# E-41_LIDAR_Dev_Brd.net
KiCad netlist of a schematic drawn in Altium Designer
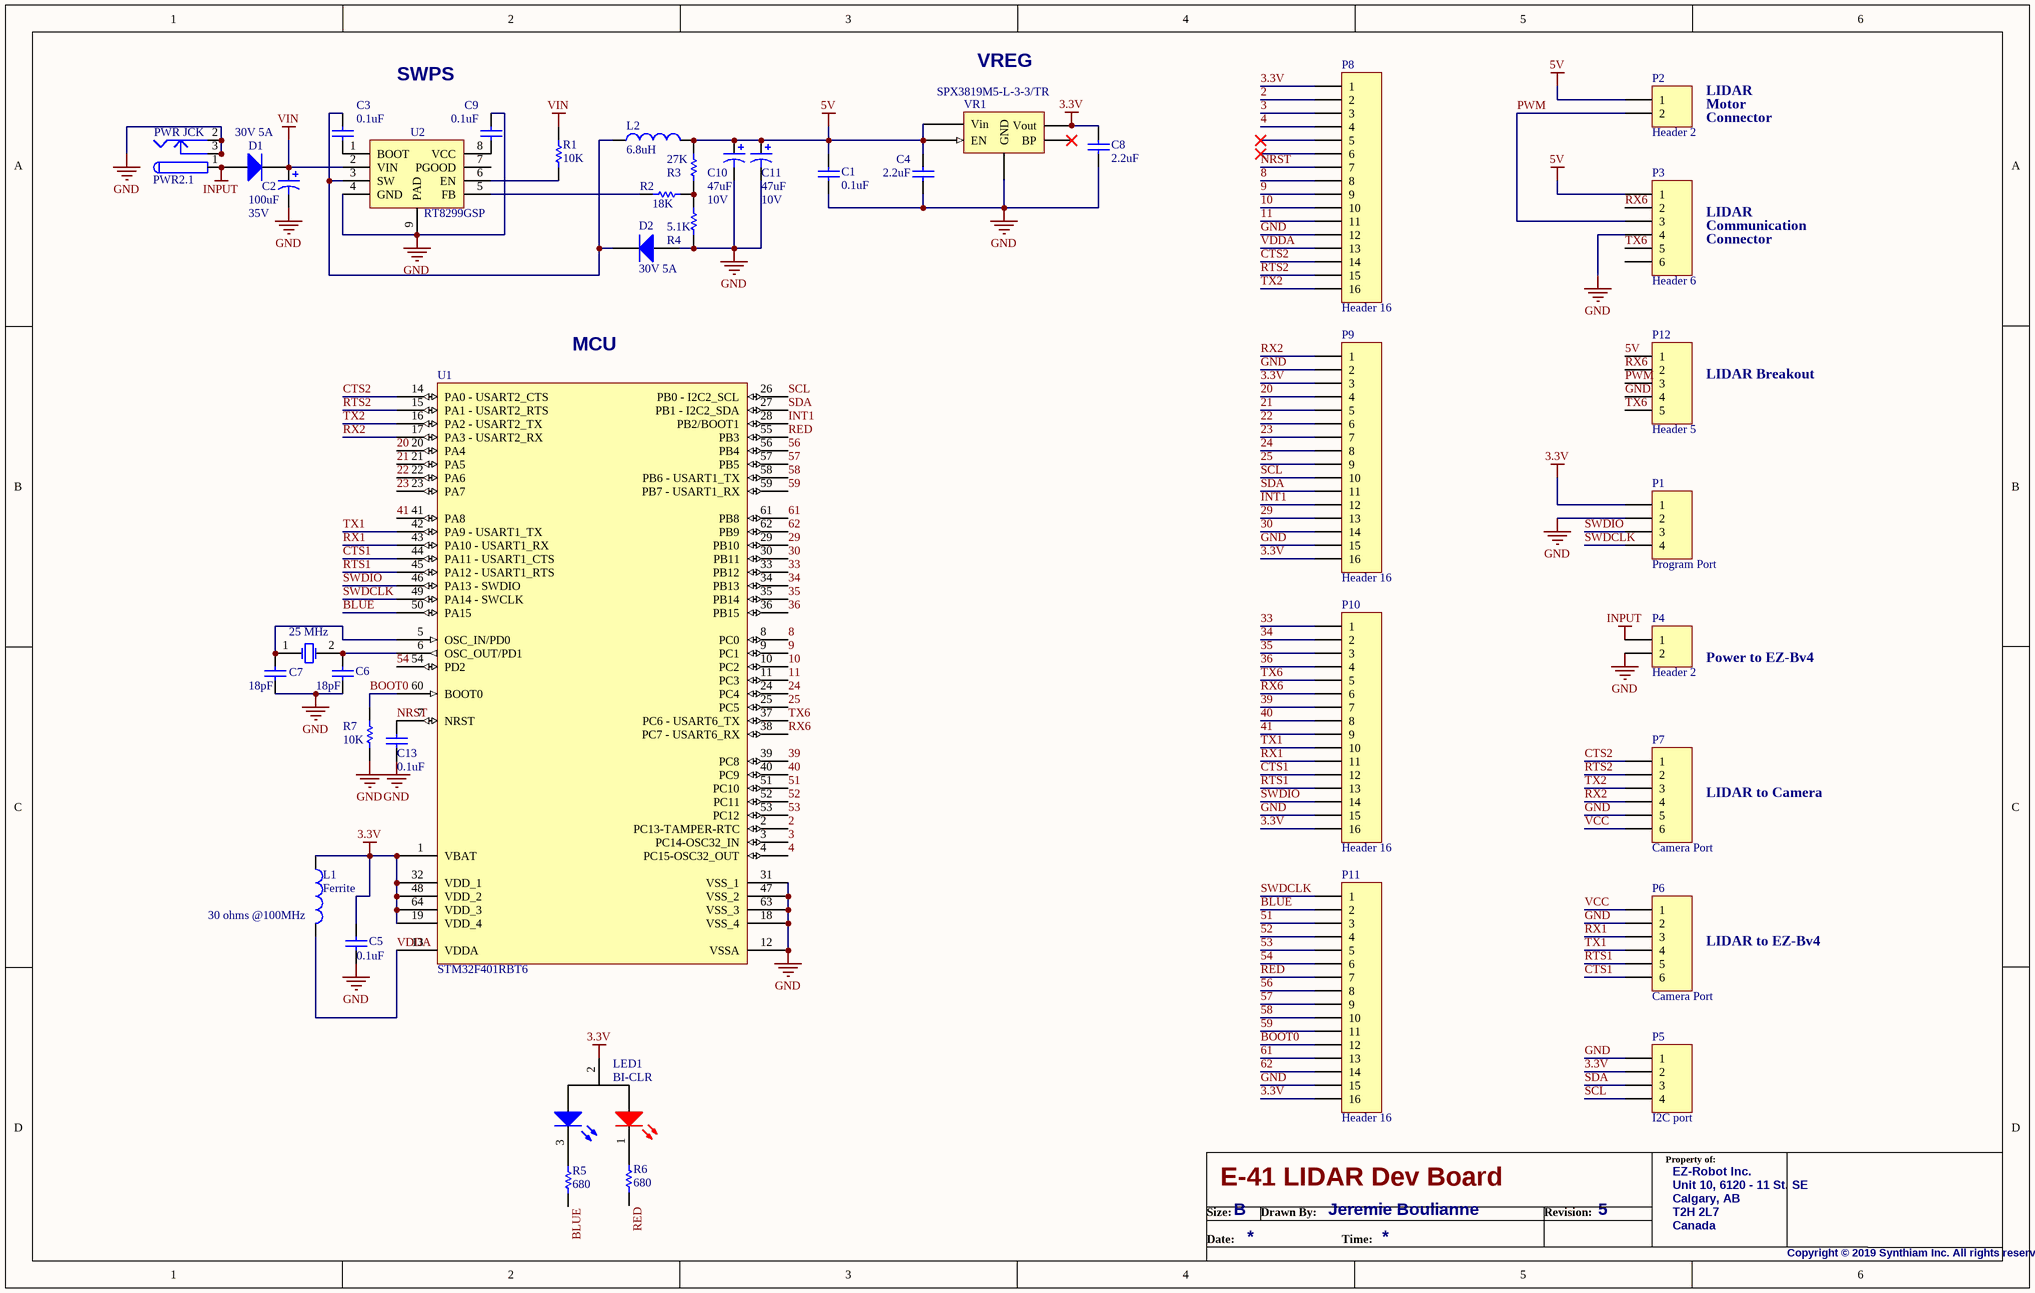
[diagram p0: E-41 LIDAR Dev Brd.SchDoc]

(export (version "E")
  (design (tool "Eeschema 10.0.6"))
  (components
    (comp (ref "25 MHz")
      (value "XTAL")
      (footprint "Crystal")
      (description "Crystal Oscillator")
      (fields (field (name "PUBLISHER") "Altium Limited"))
      (libsource (lib "SB_Discrete") (part "XTAL"))
    )
    (comp (ref "C1")
      (value "0.1uF")
      (footprint "0603 TIGHT")
      (description "Capacitor")
      (fields (field (name "Comment") "Cap") (field (name "PUBLISHER") "Altium Limited"))
      (libsource (lib "SB_Discrete") (part "Cap"))
    )
    (comp (ref "C2")
      (value "35V")
      (footprint "SMD Capacitor 220uf 16V")
      (description "Polarized Capacitor (Radial)")
      (fields (field (name "ALTIUM_VALUE") "100uF") (field (name "PUBLISHER") "Altium Limited"))
      (libsource (lib "Miscellaneous Devices") (part "Cap Pol1"))
    )
    (comp (ref "C3")
      (value "0.1uF")
      (footprint "0603 TIGHT")
      (description "Capacitor")
      (fields (field (name "PUBLISHER") "Altium Limited"))
      (libsource (lib "SB_Discrete") (part "Cap"))
    )
    (comp (ref "C4")
      (value "2.2uF")
      (footprint "0603 TIGHT")
      (description "Capacitor")
      (fields (field (name "Comment") "Cap") (field (name "PUBLISHER") "Altium Limited"))
      (libsource (lib "SB_Discrete") (part "Cap"))
    )
    (comp (ref "C5")
      (value "0.1uF")
      (footprint "0603 TIGHT")
      (description "Capacitor")
      (fields (field (name "Comment") "Cap") (field (name "PUBLISHER") "Altium Limited"))
      (libsource (lib "SB_Discrete") (part "Cap"))
    )
    (comp (ref "C6")
      (value "18pF")
      (footprint "0603 TIGHT")
      (description "Capacitor")
      (fields (field (name "Comment") "Cap") (field (name "PUBLISHER") "Altium Limited"))
      (libsource (lib "SB_Discrete") (part "Cap"))
    )
    (comp (ref "C7")
      (value "18pF")
      (footprint "0603 TIGHT")
      (description "Capacitor")
      (fields (field (name "Comment") "Cap") (field (name "PUBLISHER") "Altium Limited"))
      (libsource (lib "SB_Discrete") (part "Cap"))
    )
    (comp (ref "C8")
      (value "2.2uF")
      (footprint "0603 TIGHT")
      (description "Capacitor")
      (fields (field (name "Comment") "Cap") (field (name "PUBLISHER") "Altium Limited"))
      (libsource (lib "SB_Discrete") (part "Cap"))
    )
    (comp (ref "C9")
      (value "0.1uF")
      (footprint "0603 TIGHT")
      (description "Capacitor")
      (fields (field (name "Comment") "Cap") (field (name "PUBLISHER") "Altium Limited"))
      (libsource (lib "SB_Discrete") (part "Cap"))
    )
    (comp (ref "C10")
      (value "10V")
      (footprint "1206")
      (description "Polarized Capacitor (Radial)")
      (fields (field (name "ALTIUM_VALUE") "47uF") (field (name "PUBLISHER") "Altium Limited"))
      (libsource (lib "Miscellaneous Devices") (part "Cap Pol1"))
    )
    (comp (ref "C11")
      (value "10V")
      (footprint "1206")
      (description "Polarized Capacitor (Radial)")
      (fields (field (name "ALTIUM_VALUE") "47uF") (field (name "PUBLISHER") "Altium Limited"))
      (libsource (lib "Miscellaneous Devices") (part "Cap Pol1"))
    )
    (comp (ref "C13")
      (value "0.1uF")
      (footprint "0603 TIGHT")
      (description "Capacitor")
      (fields (field (name "Comment") "Cap") (field (name "PUBLISHER") "Altium Limited"))
      (libsource (lib "SB_Discrete") (part "Cap"))
    )
    (comp (ref "D1")
      (value "30V 5A")
      (footprint "DIODE SOD-128")
      (description "High Conductance Fast Diode")
      (fields (field (name "PUBLISHER") "Altium Limited"))
      (libsource (lib "Miscellaneous Devices") (part "Diode 1N4148"))
    )
    (comp (ref "D2")
      (value "30V 5A")
      (footprint "DIODE SOD-128")
      (description "High Conductance Fast Diode")
      (fields (field (name "PUBLISHER") "Altium Limited"))
      (libsource (lib "Miscellaneous Devices") (part "Diode 1N4148"))
    )
    (comp (ref "L1")
      (value "Ferrite")
      (footprint "0603 TIGHT")
      (description "Inductor")
      (fields (field (name "ALTIUM_VALUE") "30 ohms @100MHz") (field (name "PUBLISHER") "Altium Limited"))
      (libsource (lib "Miscellaneous Devices") (part "Inductor"))
    )
    (comp (ref "L2")
      (value "6.8uH")
      (footprint "Inductor SMD")
      (description "Inductor")
      (fields (field (name "Comment") "Ferrite") (field (name "PUBLISHER") "Altium Limited"))
      (libsource (lib "Miscellaneous Devices") (part "Inductor"))
    )
    (comp (ref "LED1")
      (value "BI-CLR")
      (footprint "LED BI-COLOR")
      (libsource (lib "SB_Discrete") (part "LED BI-COLOR"))
    )
    (comp (ref "P1")
      (value "Program Port")
      (footprint "HDR1X4")
      (description "Header, 4-Pin")
      (fields (field (name "PUBLISHER") "Altium Limited"))
      (libsource (lib "Miscellaneous Connectors") (part "Header 4"))
    )
    (comp (ref "P2")
      (value "Header 2")
      (footprint "JST-PH 2-pin")
      (description "Header, 2-Pin")
      (fields (field (name "PUBLISHER") "Altium Limited"))
      (libsource (lib "Miscellaneous Connectors") (part "Header 2"))
    )
    (comp (ref "P3")
      (value "Header 6")
      (footprint "JST-GH 6-pin")
      (description "Header, 6-Pin")
      (fields (field (name "PUBLISHER") "Altium Limited"))
      (libsource (lib "Miscellaneous Connectors") (part "Header 6"))
    )
    (comp (ref "P4")
      (value "Header 2")
      (footprint "HDR1X2")
      (description "Header, 2-Pin")
      (fields (field (name "PUBLISHER") "Altium Limited"))
      (libsource (lib "Miscellaneous Connectors") (part "Header 2"))
    )
    (comp (ref "P5")
      (value "I2C port")
      (footprint "JST-PH 4pin")
      (description "Header, 4-Pin")
      (fields (field (name "PUBLISHER") "Altium Limited"))
      (libsource (lib "Miscellaneous Connectors") (part "Header 4"))
    )
    (comp (ref "P6")
      (value "Camera Port")
      (footprint "JST-PH 6pin")
      (description "Header, 6-Pin")
      (fields (field (name "PUBLISHER") "Altium Limited"))
      (libsource (lib "Miscellaneous Connectors") (part "Header 6"))
    )
    (comp (ref "P7")
      (value "Camera Port")
      (footprint "JST-PH 6pin")
      (description "Header, 6-Pin")
      (fields (field (name "PUBLISHER") "Altium Limited"))
      (libsource (lib "Miscellaneous Connectors") (part "Header 6"))
    )
    (comp (ref "P8")
      (value "Header 16")
      (footprint "HDR1X16")
      (description "Header, 16-Pin")
      (fields (field (name "PUBLISHER") "Altium Limited"))
      (libsource (lib "Miscellaneous Connectors") (part "Header 16"))
    )
    (comp (ref "P9")
      (value "Header 16")
      (footprint "HDR1X16")
      (description "Header, 16-Pin")
      (fields (field (name "PUBLISHER") "Altium Limited"))
      (libsource (lib "Miscellaneous Connectors") (part "Header 16"))
    )
    (comp (ref "P10")
      (value "Header 16")
      (footprint "HDR1X16")
      (description "Header, 16-Pin")
      (fields (field (name "PUBLISHER") "Altium Limited"))
      (libsource (lib "Miscellaneous Connectors") (part "Header 16"))
    )
    (comp (ref "P11")
      (value "Header 16")
      (footprint "HDR1X16")
      (description "Header, 16-Pin")
      (fields (field (name "PUBLISHER") "Altium Limited"))
      (libsource (lib "Miscellaneous Connectors") (part "Header 16"))
    )
    (comp (ref "P12")
      (value "Header 5")
      (footprint "HDR1X5")
      (description "Header, 5-Pin")
      (fields (field (name "PUBLISHER") "Altium Limited"))
      (libsource (lib "Miscellaneous Connectors") (part "Header 5"))
    )
    (comp (ref "PWR JCK")
      (value "PWR2.1")
      (footprint "POWER JACK SLOTS")
      (description "Low Voltage Power Supply Connector")
      (fields (field (name "PUBLISHER") "Altium Limited"))
      (libsource (lib "Miscellaneous Connectors") (part "PWR2.5"))
    )
    (comp (ref "R1")
      (value "10K")
      (footprint "0603 TIGHT")
      (description "Resistor")
      (fields (field (name "Comment") "Res1") (field (name "PUBLISHER") "Altium Limited"))
      (libsource (lib "SB_Discrete") (part "Res1"))
    )
    (comp (ref "R2")
      (value "18K")
      (footprint "0603 TIGHT")
      (description "Resistor")
      (fields (field (name "Comment") "Res1") (field (name "PUBLISHER") "Altium Limited"))
      (libsource (lib "SB_Discrete") (part "Res1"))
    )
    (comp (ref "R3")
      (value "27K")
      (footprint "0603 TIGHT")
      (description "Resistor")
      (fields (field (name "Comment") "Res1") (field (name "PUBLISHER") "Altium Limited"))
      (libsource (lib "SB_Discrete") (part "Res1"))
    )
    (comp (ref "R4")
      (value "5.1K")
      (footprint "0603 TIGHT")
      (description "Resistor")
      (fields (field (name "Comment") "Res1") (field (name "PUBLISHER") "Altium Limited"))
      (libsource (lib "SB_Discrete") (part "Res1"))
    )
    (comp (ref "R5")
      (value "680")
      (footprint "0603 TIGHT")
      (description "Resistor")
      (fields (field (name "Comment") "Res1") (field (name "PUBLISHER") "Altium Limited"))
      (libsource (lib "SB_Discrete") (part "Res1"))
    )
    (comp (ref "R6")
      (value "680")
      (footprint "0603 TIGHT")
      (description "Resistor")
      (fields (field (name "Comment") "Res1") (field (name "PUBLISHER") "Altium Limited"))
      (libsource (lib "SB_Discrete") (part "Res1"))
    )
    (comp (ref "R7")
      (value "10K")
      (footprint "0603 TIGHT")
      (description "Resistor")
      (fields (field (name "Comment") "Res1") (field (name "PUBLISHER") "Altium Limited"))
      (libsource (lib "SB_Discrete") (part "Res1"))
    )
    (comp (ref "U1")
      (value "STM32F401RBT6")
      (footprint "LQFP64_M")
      (description "STM32 ARM MCU")
      (fields (field (name "PUBLISHER") "Altium Limited"))
      (libsource (lib "ezrobot") (part "STM32F401R8T6"))
    )
    (comp (ref "U2")
      (value "RT8299GSP")
      (footprint "SOP-8")
      (libsource (lib "SB_Engineered_Components") (part "RT8299"))
    )
    (comp (ref "VR1")
      (value "SPX3819M5-L-3-3/TR")
      (footprint "SOT-25")
      (libsource (lib "SB_Discrete") (part "Vreg SOT25"))
    )
  )
  (nets
    (net (code "1") (name "/2") (class "Default")
      (node (ref "P8") (pin "2") (pinfunction "2_2") (pintype "passive"))
      (node (ref "U1") (pin "2") (pinfunction "PC13-TAMPER-RTC_2") (pintype "bidirectional"))
    )
    (net (code "2") (name "/3") (class "Default")
      (node (ref "P8") (pin "3") (pinfunction "3_3") (pintype "passive"))
      (node (ref "U1") (pin "3") (pinfunction "PC14-OSC32_IN_3") (pintype "bidirectional"))
    )
    (net (code "3") (name "/4") (class "Default")
      (node (ref "P8") (pin "4") (pinfunction "4_4") (pintype "passive"))
      (node (ref "U1") (pin "4") (pinfunction "PC15-OSC32_OUT_4") (pintype "bidirectional"))
    )
    (net (code "4") (name "/8") (class "Default")
      (node (ref "P8") (pin "8") (pinfunction "8_8") (pintype "passive"))
      (node (ref "U1") (pin "8") (pinfunction "PC0_8") (pintype "bidirectional"))
    )
    (net (code "5") (name "/9") (class "Default")
      (node (ref "P8") (pin "9") (pinfunction "9_9") (pintype "passive"))
      (node (ref "U1") (pin "9") (pinfunction "PC1_9") (pintype "bidirectional"))
    )
    (net (code "6") (name "/10") (class "Default")
      (node (ref "P8") (pin "10") (pinfunction "10_10") (pintype "passive"))
      (node (ref "U1") (pin "10") (pinfunction "PC2_10") (pintype "bidirectional"))
    )
    (net (code "7") (name "/11") (class "Default")
      (node (ref "P8") (pin "11") (pinfunction "11_11") (pintype "passive"))
      (node (ref "U1") (pin "11") (pinfunction "PC3_11") (pintype "bidirectional"))
    )
    (net (code "8") (name "/20") (class "Default")
      (node (ref "P9") (pin "4") (pinfunction "4_4") (pintype "passive"))
      (node (ref "U1") (pin "20") (pinfunction "PA4_20") (pintype "bidirectional"))
    )
    (net (code "9") (name "/21") (class "Default")
      (node (ref "P9") (pin "5") (pinfunction "5_5") (pintype "passive"))
      (node (ref "U1") (pin "21") (pinfunction "PA5_21") (pintype "bidirectional"))
    )
    (net (code "10") (name "/22") (class "Default")
      (node (ref "P9") (pin "6") (pinfunction "6_6") (pintype "passive"))
      (node (ref "U1") (pin "22") (pinfunction "PA6_22") (pintype "bidirectional"))
    )
    (net (code "11") (name "/23") (class "Default")
      (node (ref "P9") (pin "7") (pinfunction "7_7") (pintype "passive"))
      (node (ref "U1") (pin "23") (pinfunction "PA7_23") (pintype "bidirectional"))
    )
    (net (code "12") (name "/24") (class "Default")
      (node (ref "P9") (pin "8") (pinfunction "8_8") (pintype "passive"))
      (node (ref "U1") (pin "24") (pinfunction "PC4_24") (pintype "bidirectional"))
    )
    (net (code "13") (name "/25") (class "Default")
      (node (ref "P9") (pin "9") (pinfunction "9_9") (pintype "passive"))
      (node (ref "U1") (pin "25") (pinfunction "PC5_25") (pintype "bidirectional"))
    )
    (net (code "14") (name "/29") (class "Default")
      (node (ref "P9") (pin "13") (pinfunction "13_13") (pintype "passive"))
      (node (ref "U1") (pin "29") (pinfunction "PB10_29") (pintype "bidirectional"))
    )
    (net (code "15") (name "/30") (class "Default")
      (node (ref "P9") (pin "14") (pinfunction "14_14") (pintype "passive"))
      (node (ref "U1") (pin "30") (pinfunction "PB11_30") (pintype "bidirectional"))
    )
    (net (code "16") (name "/33") (class "Default")
      (node (ref "P10") (pin "1") (pinfunction "1_1") (pintype "passive"))
      (node (ref "U1") (pin "33") (pinfunction "PB12_33") (pintype "bidirectional"))
    )
    (net (code "17") (name "/34") (class "Default")
      (node (ref "P10") (pin "2") (pinfunction "2_2") (pintype "passive"))
      (node (ref "U1") (pin "34") (pinfunction "PB13_34") (pintype "bidirectional"))
    )
    (net (code "18") (name "/35") (class "Default")
      (node (ref "P10") (pin "3") (pinfunction "3_3") (pintype "passive"))
      (node (ref "U1") (pin "35") (pinfunction "PB14_35") (pintype "bidirectional"))
    )
    (net (code "19") (name "/36") (class "Default")
      (node (ref "P10") (pin "4") (pinfunction "4_4") (pintype "passive"))
      (node (ref "U1") (pin "36") (pinfunction "PB15_36") (pintype "bidirectional"))
    )
    (net (code "20") (name "/39") (class "Default")
      (node (ref "P10") (pin "7") (pinfunction "7_7") (pintype "passive"))
      (node (ref "U1") (pin "39") (pinfunction "PC8_39") (pintype "bidirectional"))
    )
    (net (code "21") (name "/40") (class "Default")
      (node (ref "P10") (pin "8") (pinfunction "8_8") (pintype "passive"))
      (node (ref "U1") (pin "40") (pinfunction "PC9_40") (pintype "bidirectional"))
    )
    (net (code "22") (name "/41") (class "Default")
      (node (ref "P10") (pin "9") (pinfunction "9_9") (pintype "passive"))
      (node (ref "U1") (pin "41") (pinfunction "PA8_41") (pintype "bidirectional"))
    )
    (net (code "23") (name "/51") (class "Default")
      (node (ref "P11") (pin "3") (pinfunction "3_3") (pintype "passive"))
      (node (ref "U1") (pin "51") (pinfunction "PC10_51") (pintype "bidirectional"))
    )
    (net (code "24") (name "/52") (class "Default")
      (node (ref "P11") (pin "4") (pinfunction "4_4") (pintype "passive"))
      (node (ref "U1") (pin "52") (pinfunction "PC11_52") (pintype "bidirectional"))
    )
    (net (code "25") (name "/53") (class "Default")
      (node (ref "P11") (pin "5") (pinfunction "5_5") (pintype "passive"))
      (node (ref "U1") (pin "53") (pinfunction "PC12_53") (pintype "bidirectional"))
    )
    (net (code "26") (name "/54") (class "Default")
      (node (ref "P11") (pin "6") (pinfunction "6_6") (pintype "passive"))
      (node (ref "U1") (pin "54") (pinfunction "PD2_54") (pintype "bidirectional"))
    )
    (net (code "27") (name "/56") (class "Default")
      (node (ref "P11") (pin "8") (pinfunction "8_8") (pintype "passive"))
      (node (ref "U1") (pin "56") (pinfunction "PB4_56") (pintype "bidirectional"))
    )
    (net (code "28") (name "/57") (class "Default")
      (node (ref "P11") (pin "9") (pinfunction "9_9") (pintype "passive"))
      (node (ref "U1") (pin "57") (pinfunction "PB5_57") (pintype "bidirectional"))
    )
    (net (code "29") (name "/58") (class "Default")
      (node (ref "P11") (pin "10") (pinfunction "10_10") (pintype "passive"))
      (node (ref "U1") (pin "58") (pinfunction "PB6_-_USART1_TX_58") (pintype "bidirectional"))
    )
    (net (code "30") (name "/59") (class "Default")
      (node (ref "P11") (pin "11") (pinfunction "11_11") (pintype "passive"))
      (node (ref "U1") (pin "59") (pinfunction "PB7_-_USART1_RX_59") (pintype "bidirectional"))
    )
    (net (code "31") (name "/61") (class "Default")
      (node (ref "P11") (pin "13") (pinfunction "13_13") (pintype "passive"))
      (node (ref "U1") (pin "61") (pinfunction "PB8_61") (pintype "bidirectional"))
    )
    (net (code "32") (name "/62") (class "Default")
      (node (ref "P11") (pin "14") (pinfunction "14_14") (pintype "passive"))
      (node (ref "U1") (pin "62") (pinfunction "PB9_62") (pintype "bidirectional"))
    )
    (net (code "33") (name "/BLUE") (class "Default")
      (node (ref "P11") (pin "2") (pinfunction "2_2") (pintype "passive"))
      (node (ref "R5") (pin "1") (pinfunction "1_1") (pintype "passive"))
      (node (ref "U1") (pin "50") (pinfunction "PA15_50") (pintype "bidirectional"))
    )
    (net (code "34") (name "/BOOT0") (class "Default")
      (node (ref "P11") (pin "12") (pinfunction "12_12") (pintype "passive"))
      (node (ref "R7") (pin "2") (pinfunction "2_2") (pintype "passive"))
      (node (ref "U1") (pin "60") (pinfunction "BOOT0_60") (pintype "input"))
    )
    (net (code "35") (name "/CTS1") (class "Default")
      (node (ref "P10") (pin "12") (pinfunction "12_12") (pintype "passive"))
      (node (ref "P6") (pin "6") (pinfunction "6_6") (pintype "passive"))
      (node (ref "U1") (pin "44") (pinfunction "PA11_-_USART1_CTS_44") (pintype "bidirectional"))
    )
    (net (code "36") (name "/CTS2") (class "Default")
      (node (ref "P7") (pin "1") (pinfunction "1_1") (pintype "passive"))
      (node (ref "P8") (pin "14") (pinfunction "14_14") (pintype "passive"))
      (node (ref "U1") (pin "14") (pinfunction "PA0_-_USART2_CTS_14") (pintype "bidirectional"))
    )
    (net (code "37") (name "/INT1") (class "Default")
      (node (ref "P9") (pin "12") (pinfunction "12_12") (pintype "passive"))
      (node (ref "U1") (pin "28") (pinfunction "PB2/BOOT1_28") (pintype "bidirectional"))
    )
    (net (code "38") (name "/NRST") (class "Default")
      (node (ref "C13") (pin "1") (pinfunction "1_1") (pintype "passive"))
      (node (ref "P8") (pin "7") (pinfunction "7_7") (pintype "passive"))
      (node (ref "U1") (pin "7") (pinfunction "NRST_7") (pintype "bidirectional"))
    )
    (net (code "39") (name "/PWM") (class "Default")
      (node (ref "P12") (pin "3") (pinfunction "3_3") (pintype "passive"))
      (node (ref "P2") (pin "2") (pinfunction "2_2") (pintype "passive"))
      (node (ref "P3") (pin "3") (pinfunction "3_3") (pintype "passive"))
    )
    (net (code "40") (name "/RED") (class "Default")
      (node (ref "P11") (pin "7") (pinfunction "7_7") (pintype "passive"))
      (node (ref "R6") (pin "1") (pinfunction "1_1") (pintype "passive"))
      (node (ref "U1") (pin "55") (pinfunction "PB3_55") (pintype "bidirectional"))
    )
    (net (code "41") (name "/RTS1") (class "Default")
      (node (ref "P10") (pin "13") (pinfunction "13_13") (pintype "passive"))
      (node (ref "P6") (pin "5") (pinfunction "5_5") (pintype "passive"))
      (node (ref "U1") (pin "45") (pinfunction "PA12_-_USART1_RTS_45") (pintype "bidirectional"))
    )
    (net (code "42") (name "/RTS2") (class "Default")
      (node (ref "P7") (pin "2") (pinfunction "2_2") (pintype "passive"))
      (node (ref "P8") (pin "15") (pinfunction "15_15") (pintype "passive"))
      (node (ref "U1") (pin "15") (pinfunction "PA1_-_USART2_RTS_15") (pintype "bidirectional"))
    )
    (net (code "43") (name "/RX1") (class "Default")
      (node (ref "P10") (pin "11") (pinfunction "11_11") (pintype "passive"))
      (node (ref "P6") (pin "3") (pinfunction "3_3") (pintype "passive"))
      (node (ref "U1") (pin "43") (pinfunction "PA10_-_USART1_RX_43") (pintype "bidirectional"))
    )
    (net (code "44") (name "/RX2") (class "Default")
      (node (ref "P7") (pin "4") (pinfunction "4_4") (pintype "passive"))
      (node (ref "P9") (pin "1") (pinfunction "1_1") (pintype "passive"))
      (node (ref "U1") (pin "17") (pinfunction "PA3_-_USART2_RX_17") (pintype "bidirectional"))
    )
    (net (code "45") (name "/RX6") (class "Default")
      (node (ref "P10") (pin "6") (pinfunction "6_6") (pintype "passive"))
      (node (ref "P12") (pin "2") (pinfunction "2_2") (pintype "passive"))
      (node (ref "P3") (pin "2") (pinfunction "2_2") (pintype "passive"))
      (node (ref "U1") (pin "38") (pinfunction "PC7_-_USART6_RX_38") (pintype "bidirectional"))
    )
    (net (code "46") (name "/SCL") (class "Default")
      (node (ref "P5") (pin "4") (pinfunction "4_4") (pintype "passive"))
      (node (ref "P9") (pin "10") (pinfunction "10_10") (pintype "passive"))
      (node (ref "U1") (pin "26") (pinfunction "PB0_-_I2C2_SCL_26") (pintype "bidirectional"))
    )
    (net (code "47") (name "/SDA") (class "Default")
      (node (ref "P5") (pin "3") (pinfunction "3_3") (pintype "passive"))
      (node (ref "P9") (pin "11") (pinfunction "11_11") (pintype "passive"))
      (node (ref "U1") (pin "27") (pinfunction "PB1_-_I2C2_SDA_27") (pintype "bidirectional"))
    )
    (net (code "48") (name "/SWDCLK") (class "Default")
      (node (ref "P1") (pin "4") (pinfunction "4_4") (pintype "passive"))
      (node (ref "P11") (pin "1") (pinfunction "1_1") (pintype "passive"))
      (node (ref "U1") (pin "49") (pinfunction "PA14_-_SWCLK_49") (pintype "bidirectional"))
    )
    (net (code "49") (name "/SWDIO") (class "Default")
      (node (ref "P1") (pin "3") (pinfunction "3_3") (pintype "passive"))
      (node (ref "P10") (pin "14") (pinfunction "14_14") (pintype "passive"))
      (node (ref "U1") (pin "46") (pinfunction "PA13_-_SWDIO_46") (pintype "bidirectional"))
    )
    (net (code "50") (name "/TX1") (class "Default")
      (node (ref "P10") (pin "10") (pinfunction "10_10") (pintype "passive"))
      (node (ref "P6") (pin "4") (pinfunction "4_4") (pintype "passive"))
      (node (ref "U1") (pin "42") (pinfunction "PA9_-_USART1_TX_42") (pintype "bidirectional"))
    )
    (net (code "51") (name "/TX2") (class "Default")
      (node (ref "P7") (pin "3") (pinfunction "3_3") (pintype "passive"))
      (node (ref "P8") (pin "16") (pinfunction "16_16") (pintype "passive"))
      (node (ref "U1") (pin "16") (pinfunction "PA2_-_USART2_TX_16") (pintype "bidirectional"))
    )
    (net (code "52") (name "/TX6") (class "Default")
      (node (ref "P10") (pin "5") (pinfunction "5_5") (pintype "passive"))
      (node (ref "P12") (pin "5") (pinfunction "5_5") (pintype "passive"))
      (node (ref "P3") (pin "5") (pinfunction "5_5") (pintype "passive"))
      (node (ref "U1") (pin "37") (pinfunction "PC6_-_USART6_TX_37") (pintype "bidirectional"))
    )
    (net (code "53") (name "/VCC") (class "Default")
      (node (ref "P6") (pin "1") (pinfunction "1_1") (pintype "passive"))
      (node (ref "P7") (pin "6") (pinfunction "6_6") (pintype "passive"))
    )
    (net (code "54") (name "/VDDA") (class "Default")
      (node (ref "L1") (pin "2") (pinfunction "2_2") (pintype "passive"))
      (node (ref "P8") (pin "13") (pinfunction "13_13") (pintype "passive"))
      (node (ref "U1") (pin "13") (pinfunction "VDDA_13") (pintype "power_in"))
    )
    (net (code "55") (name "3.3V") (class "Default")
      (node (ref "C5") (pin "1") (pinfunction "1_1") (pintype "passive"))
      (node (ref "C8") (pin "1") (pinfunction "1_1") (pintype "passive"))
      (node (ref "L1") (pin "1") (pinfunction "1_1") (pintype "passive"))
      (node (ref "LED1") (pin "2") (pinfunction "2_2") (pintype "passive"))
      (node (ref "P1") (pin "1") (pinfunction "1_1") (pintype "passive"))
      (node (ref "P10") (pin "16") (pinfunction "16_16") (pintype "passive"))
      (node (ref "P11") (pin "16") (pinfunction "16_16") (pintype "passive"))
      (node (ref "P5") (pin "2") (pinfunction "2_2") (pintype "passive"))
      (node (ref "P8") (pin "1") (pinfunction "1_1") (pintype "passive"))
      (node (ref "P9") (pin "16") (pinfunction "16_16") (pintype "passive"))
      (node (ref "P9") (pin "3") (pinfunction "3_3") (pintype "passive"))
      (node (ref "U1") (pin "1") (pinfunction "VBAT_1") (pintype "power_in"))
      (node (ref "U1") (pin "19") (pinfunction "VDD_4_19") (pintype "power_in"))
      (node (ref "U1") (pin "32") (pinfunction "VDD_1_32") (pintype "power_in"))
      (node (ref "U1") (pin "48") (pinfunction "VDD_2_48") (pintype "power_in"))
      (node (ref "U1") (pin "64") (pinfunction "VDD_3_64") (pintype "power_in"))
      (node (ref "VR1") (pin "2") (pinfunction "Vout_2") (pintype "passive"))
    )
    (net (code "56") (name "5V") (class "Default")
      (node (ref "C1") (pin "1") (pinfunction "1_1") (pintype "passive"))
      (node (ref "C10") (pin "1") (pinfunction "1_1") (pintype "passive"))
      (node (ref "C11") (pin "1") (pinfunction "1_1") (pintype "passive"))
      (node (ref "C4") (pin "1") (pinfunction "1_1") (pintype "passive"))
      (node (ref "L2") (pin "2") (pinfunction "2_2") (pintype "passive"))
      (node (ref "P12") (pin "1") (pinfunction "1_1") (pintype "passive"))
      (node (ref "P2") (pin "1") (pinfunction "1_1") (pintype "passive"))
      (node (ref "P3") (pin "1") (pinfunction "1_1") (pintype "passive"))
      (node (ref "R3") (pin "2") (pinfunction "2_2") (pintype "passive"))
      (node (ref "VR1") (pin "4") (pinfunction "EN_4") (pintype "input"))
      (node (ref "VR1") (pin "5") (pinfunction "Vin_5") (pintype "passive"))
    )
    (net (code "57") (name "GND") (class "Default")
      (node (ref "C1") (pin "2") (pinfunction "2_2") (pintype "passive"))
      (node (ref "C10") (pin "2") (pinfunction "2_2") (pintype "passive"))
      (node (ref "C11") (pin "2") (pinfunction "2_2") (pintype "passive"))
      (node (ref "C13") (pin "2") (pinfunction "2_2") (pintype "passive"))
      (node (ref "C2") (pin "2") (pinfunction "2_2") (pintype "passive"))
      (node (ref "C4") (pin "2") (pinfunction "2_2") (pintype "passive"))
      (node (ref "C5") (pin "2") (pinfunction "2_2") (pintype "passive"))
      (node (ref "C6") (pin "2") (pinfunction "2_2") (pintype "passive"))
      (node (ref "C7") (pin "2") (pinfunction "2_2") (pintype "passive"))
      (node (ref "C8") (pin "2") (pinfunction "2_2") (pintype "passive"))
      (node (ref "C9") (pin "1") (pinfunction "1_1") (pintype "passive"))
      (node (ref "D2") (pin "1") (pinfunction "A_1") (pintype "passive"))
      (node (ref "P1") (pin "2") (pinfunction "2_2") (pintype "passive"))
      (node (ref "P10") (pin "15") (pinfunction "15_15") (pintype "passive"))
      (node (ref "P11") (pin "15") (pinfunction "15_15") (pintype "passive"))
      (node (ref "P12") (pin "4") (pinfunction "4_4") (pintype "passive"))
      (node (ref "P3") (pin "4") (pinfunction "4_4") (pintype "passive"))
      (node (ref "P4") (pin "2") (pinfunction "2_2") (pintype "passive"))
      (node (ref "P5") (pin "1") (pinfunction "1_1") (pintype "passive"))
      (node (ref "P6") (pin "2") (pinfunction "2_2") (pintype "passive"))
      (node (ref "P7") (pin "5") (pinfunction "5_5") (pintype "passive"))
      (node (ref "P8") (pin "12") (pinfunction "12_12") (pintype "passive"))
      (node (ref "P9") (pin "15") (pinfunction "15_15") (pintype "passive"))
      (node (ref "P9") (pin "2") (pinfunction "2_2") (pintype "passive"))
      (node (ref "PWR JCK") (pin "2") (pinfunction "2_2") (pintype "power_in"))
      (node (ref "PWR JCK") (pin "2A") (pinfunction "2A_2A") (pintype "power_in"))
      (node (ref "PWR JCK") (pin "2B") (pinfunction "2B_2B") (pintype "power_in"))
      (node (ref "PWR JCK") (pin "3") (pinfunction "3_3") (pintype "power_in"))
      (node (ref "PWR JCK") (pin "3A") (pinfunction "3A_3A") (pintype "power_in"))
      (node (ref "PWR JCK") (pin "3B") (pinfunction "3B_3B") (pintype "power_in"))
      (node (ref "R4") (pin "1") (pinfunction "1_1") (pintype "passive"))
      (node (ref "R7") (pin "1") (pinfunction "1_1") (pintype "passive"))
      (node (ref "U1") (pin "12") (pinfunction "VSSA_12") (pintype "power_in"))
      (node (ref "U1") (pin "18") (pinfunction "VSS_4_18") (pintype "power_in"))
      (node (ref "U1") (pin "31") (pinfunction "VSS_1_31") (pintype "power_in"))
      (node (ref "U1") (pin "47") (pinfunction "VSS_2_47") (pintype "power_in"))
      (node (ref "U1") (pin "63") (pinfunction "VSS_3_63") (pintype "power_in"))
      (node (ref "U2") (pin "4") (pinfunction "GND_4") (pintype "power_in"))
      (node (ref "U2") (pin "9") (pinfunction "PAD_9") (pintype "passive"))
      (node (ref "VR1") (pin "3") (pinfunction "GND_3") (pintype "passive"))
    )
    (net (code "58") (name "INPUT") (class "Default")
      (node (ref "D1") (pin "1") (pinfunction "A_1") (pintype "passive"))
      (node (ref "P4") (pin "1") (pinfunction "1_1") (pintype "passive"))
      (node (ref "PWR JCK") (pin "1") (pinfunction "1_1") (pintype "power_in"))
      (node (ref "PWR JCK") (pin "1A") (pinfunction "1A_1A") (pintype "power_in"))
      (node (ref "PWR JCK") (pin "1B") (pinfunction "1B_1B") (pintype "power_in"))
    )
    (net (code "59") (name "Net-(25 MHz-OSC1)") (class "Default")
      (node (ref "25 MHz") (pin "1") (pinfunction "OSC1_1") (pintype "passive"))
      (node (ref "C7") (pin "1") (pinfunction "1_1") (pintype "passive"))
      (node (ref "U1") (pin "5") (pinfunction "OSC_IN/PD0_5") (pintype "input"))
    )
    (net (code "60") (name "Net-(25 MHz-OSC2)") (class "Default")
      (node (ref "25 MHz") (pin "2") (pinfunction "OSC2_2") (pintype "passive"))
      (node (ref "C6") (pin "1") (pinfunction "1_1") (pintype "passive"))
      (node (ref "U1") (pin "6") (pinfunction "OSC_OUT/PD1_6") (pintype "output"))
    )
    (net (code "61") (name "Net-(D2-K)") (class "Default")
      (node (ref "C3") (pin "2") (pinfunction "2_2") (pintype "passive"))
      (node (ref "D2") (pin "2") (pinfunction "K_2") (pintype "passive"))
      (node (ref "L2") (pin "1") (pinfunction "1_1") (pintype "passive"))
      (node (ref "U2") (pin "3") (pinfunction "SW_3") (pintype "passive"))
    )
    (net (code "62") (name "Net-(LED1-Pad1)") (class "Default")
      (node (ref "LED1") (pin "1") (pinfunction "1_1") (pintype "passive"))
      (node (ref "R6") (pin "2") (pinfunction "2_2") (pintype "passive"))
    )
    (net (code "63") (name "Net-(LED1-Pad3)") (class "Default")
      (node (ref "LED1") (pin "3") (pinfunction "3_3") (pintype "passive"))
      (node (ref "R5") (pin "2") (pinfunction "2_2") (pintype "passive"))
    )
    (net (code "64") (name "Net-(R2-Pad1)") (class "Default")
      (node (ref "R2") (pin "1") (pinfunction "1_1") (pintype "passive"))
      (node (ref "R3") (pin "1") (pinfunction "1_1") (pintype "passive"))
      (node (ref "R4") (pin "2") (pinfunction "2_2") (pintype "passive"))
    )
    (net (code "65") (name "Net-(U2-BOOT)") (class "Default")
      (node (ref "C3") (pin "1") (pinfunction "1_1") (pintype "passive"))
      (node (ref "U2") (pin "1") (pinfunction "BOOT_1") (pintype "power_in"))
    )
    (net (code "66") (name "Net-(U2-EN)") (class "Default")
      (node (ref "R1") (pin "1") (pinfunction "1_1") (pintype "passive"))
      (node (ref "U2") (pin "6") (pinfunction "EN_6") (pintype "passive"))
    )
    (net (code "67") (name "Net-(U2-FB)") (class "Default")
      (node (ref "R2") (pin "2") (pinfunction "2_2") (pintype "passive"))
      (node (ref "U2") (pin "5") (pinfunction "FB_5") (pintype "passive"))
    )
    (net (code "68") (name "Net-(U2-VCC)") (class "Default")
      (node (ref "C9") (pin "2") (pinfunction "2_2") (pintype "passive"))
      (node (ref "U2") (pin "8") (pinfunction "VCC_8") (pintype "power_in"))
    )
    (net (code "69") (name "VIN") (class "Default")
      (node (ref "C2") (pin "1") (pinfunction "1_1") (pintype "passive"))
      (node (ref "D1") (pin "2") (pinfunction "K_2") (pintype "passive"))
      (node (ref "R1") (pin "2") (pinfunction "2_2") (pintype "passive"))
      (node (ref "U2") (pin "2") (pinfunction "VIN_2") (pintype "power_in"))
    )
    (net (code "70") (name "unconnected-(P3-Pad6)") (class "Default")
      (node (ref "P3") (pin "6") (pinfunction "6_6") (pintype "passive"))
    )
    (net (code "71") (name "unconnected-(P8-Pad5)") (class "Default")
      (node (ref "P8") (pin "5") (pinfunction "5_5") (pintype "passive+no_connect"))
    )
    (net (code "72") (name "unconnected-(P8-Pad6)") (class "Default")
      (node (ref "P8") (pin "6") (pinfunction "6_6") (pintype "passive+no_connect"))
    )
    (net (code "73") (name "unconnected-(U2-PGOOD-Pad7)") (class "Default")
      (node (ref "U2") (pin "7") (pinfunction "PGOOD_7") (pintype "power_in"))
    )
    (net (code "74") (name "unconnected-(VR1-BP-Pad1)") (class "Default")
      (node (ref "VR1") (pin "1") (pinfunction "BP_1") (pintype "passive+no_connect"))
    )
  )
)
